# design.net
KiCad netlist of a schematic drawn in Altium Designer
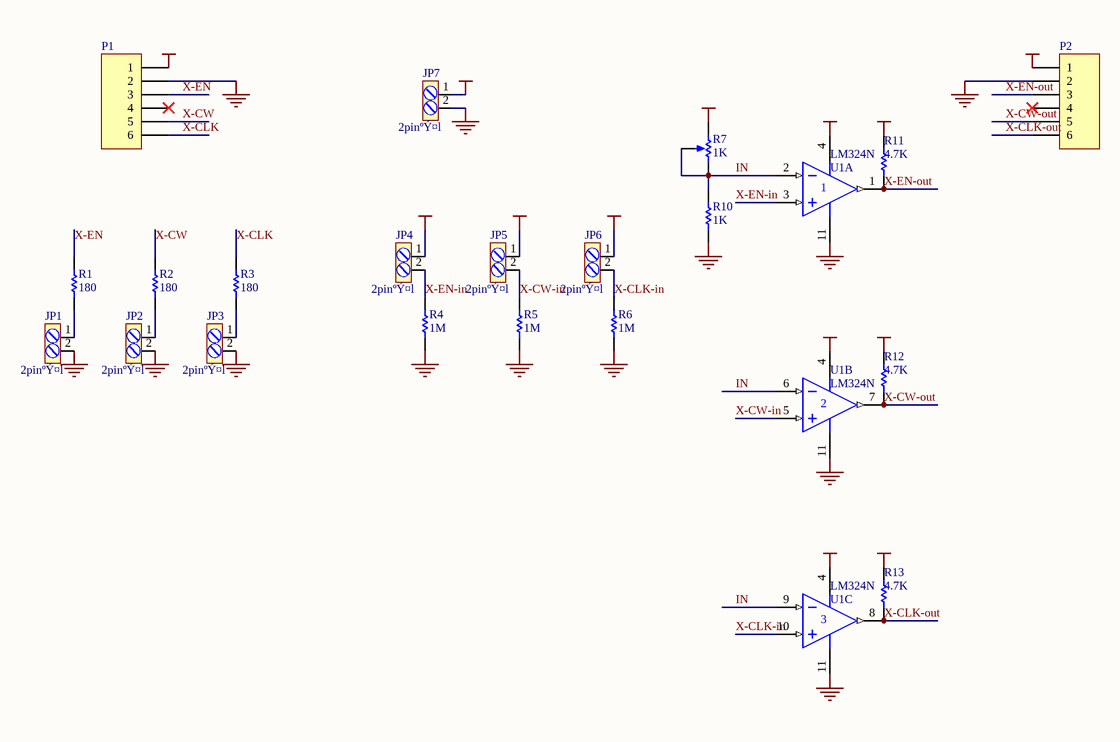
[diagram p0: 光纖發射.SCHDOC]

(export (version "E")
  (design (tool "Eeschema 10.0.6"))
  (components
    (comp (ref "JP1") (value "2pinºÝ¤l") (footprint "2PINºÝ¤l-1") (libsource (lib "") (part "2pinºÝ¤l_1")))
    (comp (ref "JP2")
      (value "2pinºÝ¤l")
      (footprint "2PINºÝ¤l-1")
      (libsource (lib "mydata") (part "2pinºÝ¤l"))
    )
    (comp (ref "JP3")
      (value "2pinºÝ¤l")
      (footprint "2PINºÝ¤l-1")
      (libsource (lib "mydata") (part "2pinºÝ¤l"))
    )
    (comp (ref "JP4")
      (value "2pinºÝ¤l")
      (footprint "2PINºÝ¤l-1")
      (libsource (lib "mydata") (part "2pinºÝ¤l"))
    )
    (comp (ref "JP5")
      (value "2pinºÝ¤l")
      (footprint "2PINºÝ¤l-1")
      (libsource (lib "mydata") (part "2pinºÝ¤l"))
    )
    (comp (ref "JP6")
      (value "2pinºÝ¤l")
      (footprint "2PINºÝ¤l-1")
      (libsource (lib "mydata") (part "2pinºÝ¤l"))
    )
    (comp (ref "JP7")
      (value "2pinºÝ¤l")
      (footprint "2PINºÝ¤l-1")
      (libsource (lib "mydata") (part "2pinºÝ¤l"))
    )
    (comp (ref "P1")
      (value "Header 6")
      (footprint "HDR1X6")
      (description "Header, 6-Pin")
      (fields (field (name "PUBLISHER") "Altium Limited"))
      (libsource (lib "") (part "Header 6_1"))
    )
    (comp (ref "P2")
      (value "Header 6")
      (footprint "HDR1X6")
      (description "Header, 6-Pin")
      (fields (field (name "PUBLISHER") "Altium Limited"))
      (libsource (lib "Miscellaneous Connectors") (part "Header 6"))
    )
    (comp (ref "R1")
      (value "180")
      (footprint "AXIAL-0.3")
      (description "Resistor")
      (fields (field (name "Comment") "Res1") (field (name "PUBLISHER") "Altium Limited"))
      (libsource (lib "Miscellaneous Devices") (part "Res1"))
    )
    (comp (ref "R2")
      (value "180")
      (footprint "AXIAL-0.3")
      (description "Resistor")
      (fields (field (name "Comment") "Res1") (field (name "PUBLISHER") "Altium Limited"))
      (libsource (lib "Miscellaneous Devices") (part "Res1"))
    )
    (comp (ref "R3")
      (value "180")
      (footprint "AXIAL-0.3")
      (description "Resistor")
      (fields (field (name "Comment") "Res1") (field (name "PUBLISHER") "Altium Limited"))
      (libsource (lib "Miscellaneous Devices") (part "Res1"))
    )
    (comp (ref "R4")
      (value "1M")
      (footprint "AXIAL-0.3")
      (description "Resistor")
      (fields (field (name "Comment") "Res1") (field (name "PUBLISHER") "Altium Limited"))
      (libsource (lib "Miscellaneous Devices") (part "Res1"))
    )
    (comp (ref "R5")
      (value "1M")
      (footprint "AXIAL-0.3")
      (description "Resistor")
      (fields (field (name "Comment") "Res1") (field (name "PUBLISHER") "Altium Limited"))
      (libsource (lib "Miscellaneous Devices") (part "Res1"))
    )
    (comp (ref "R6")
      (value "1M")
      (footprint "AXIAL-0.3")
      (description "Resistor")
      (fields (field (name "Comment") "Res1") (field (name "PUBLISHER") "Altium Limited"))
      (libsource (lib "Miscellaneous Devices") (part "Res1"))
    )
    (comp (ref "R7")
      (value "1K")
      (footprint "VR1")
      (description "Potentiometer")
      (fields (field (name "Comment") "RPot") (field (name "PUBLISHER") "Altium Limited"))
      (libsource (lib "Miscellaneous Devices") (part "RPot"))
    )
    (comp (ref "R10")
      (value "1K")
      (footprint "AXIAL-0.3")
      (description "Resistor")
      (fields (field (name "Comment") "Res1") (field (name "PUBLISHER") "Altium Limited"))
      (libsource (lib "Miscellaneous Devices") (part "Res1"))
    )
    (comp (ref "R11")
      (value "4.7K")
      (footprint "AXIAL-0.3")
      (description "Resistor")
      (fields (field (name "Comment") "Res1") (field (name "PUBLISHER") "Altium Limited"))
      (libsource (lib "Miscellaneous Devices") (part "Res1"))
    )
    (comp (ref "R12")
      (value "4.7K")
      (footprint "AXIAL-0.3")
      (description "Resistor")
      (fields (field (name "Comment") "Res1") (field (name "PUBLISHER") "Altium Limited"))
      (libsource (lib "Miscellaneous Devices") (part "Res1"))
    )
    (comp (ref "R13")
      (value "4.7K")
      (footprint "AXIAL-0.3")
      (description "Resistor")
      (fields (field (name "Comment") "Res1") (field (name "PUBLISHER") "Altium Limited"))
      (libsource (lib "Miscellaneous Devices") (part "Res1"))
    )
    (comp (ref "U1")
      (value "LM324N")
      (footprint "646-06")
      (description "Quad Low-Power Operational Amplifier")
      (fields (field (name "PUBLISHER") "Altium Limited"))
      (libsource (lib "Motorola Amplifier Operational Amplifier") (part "LM324N"))
    )
  )
  (nets
    (net (code "1") (name "+5") (class "Default")
      (node (ref "JP4") (pin "1") (pinfunction "1_1") (pintype "passive"))
      (node (ref "JP5") (pin "1") (pinfunction "1_1") (pintype "passive"))
      (node (ref "JP6") (pin "1") (pinfunction "1_1") (pintype "passive"))
      (node (ref "JP7") (pin "1") (pinfunction "1_1") (pintype "passive"))
      (node (ref "P2") (pin "1") (pinfunction "1_1") (pintype "passive"))
      (node (ref "R11") (pin "2") (pinfunction "2_2") (pintype "passive"))
      (node (ref "R12") (pin "2") (pinfunction "2_2") (pintype "passive"))
      (node (ref "R13") (pin "2") (pinfunction "2_2") (pintype "passive"))
      (node (ref "R7") (pin "1") (pinfunction "TOP_1") (pintype "passive"))
      (node (ref "U1") (pin "4") (pinfunction "V+_4") (pintype "power_in"))
    )
    (net (code "2") (name "/IN") (class "Default")
      (node (ref "R10") (pin "2") (pinfunction "2_2") (pintype "passive"))
      (node (ref "R7") (pin "2") (pinfunction "BOT_2") (pintype "passive"))
      (node (ref "R7") (pin "3") (pinfunction "TAP_3") (pintype "passive"))
      (node (ref "U1") (pin "2") (pinfunction "IN-_2") (pintype "input"))
      (node (ref "U1") (pin "6") (pinfunction "IN-_6") (pintype "input"))
      (node (ref "U1") (pin "9") (pinfunction "IN-_9") (pintype "input"))
    )
    (net (code "3") (name "/X-CLK") (class "Default")
      (node (ref "P1") (pin "6") (pinfunction "6_6") (pintype "passive"))
      (node (ref "R3") (pin "1") (pinfunction "1_1") (pintype "passive"))
    )
    (net (code "4") (name "/X-CLK-in") (class "Default")
      (node (ref "JP6") (pin "2") (pinfunction "2_2") (pintype "passive"))
      (node (ref "R6") (pin "1") (pinfunction "1_1") (pintype "passive"))
      (node (ref "U1") (pin "10") (pinfunction "IN+_10") (pintype "input"))
    )
    (net (code "5") (name "/X-CLK-out") (class "Default")
      (node (ref "P2") (pin "6") (pinfunction "6_6") (pintype "passive"))
      (node (ref "R13") (pin "1") (pinfunction "1_1") (pintype "passive"))
      (node (ref "U1") (pin "8") (pinfunction "OUT_8") (pintype "output"))
    )
    (net (code "6") (name "/X-CW") (class "Default")
      (node (ref "P1") (pin "5") (pinfunction "5_5") (pintype "passive"))
      (node (ref "R2") (pin "1") (pinfunction "1_1") (pintype "passive"))
    )
    (net (code "7") (name "/X-CW-in") (class "Default")
      (node (ref "JP5") (pin "2") (pinfunction "2_2") (pintype "passive"))
      (node (ref "R5") (pin "1") (pinfunction "1_1") (pintype "passive"))
      (node (ref "U1") (pin "5") (pinfunction "IN+_5") (pintype "input"))
    )
    (net (code "8") (name "/X-CW-out") (class "Default")
      (node (ref "P2") (pin "5") (pinfunction "5_5") (pintype "passive"))
      (node (ref "R12") (pin "1") (pinfunction "1_1") (pintype "passive"))
      (node (ref "U1") (pin "7") (pinfunction "OUT_7") (pintype "output"))
    )
    (net (code "9") (name "/X-EN") (class "Default")
      (node (ref "P1") (pin "3") (pinfunction "3_3") (pintype "passive"))
      (node (ref "R1") (pin "2") (pinfunction "2_2") (pintype "passive"))
    )
    (net (code "10") (name "/X-EN-in") (class "Default")
      (node (ref "JP4") (pin "2") (pinfunction "2_2") (pintype "passive"))
      (node (ref "R4") (pin "1") (pinfunction "1_1") (pintype "passive"))
      (node (ref "U1") (pin "3") (pinfunction "IN+_3") (pintype "input"))
    )
    (net (code "11") (name "/X-EN-out") (class "Default")
      (node (ref "P2") (pin "3") (pinfunction "3_3") (pintype "passive"))
      (node (ref "R11") (pin "1") (pinfunction "1_1") (pintype "passive"))
      (node (ref "U1") (pin "1") (pinfunction "OUT_1") (pintype "output"))
    )
    (net (code "12") (name "GND") (class "Default")
      (node (ref "JP1") (pin "2") (pinfunction "2_2") (pintype "passive"))
      (node (ref "JP2") (pin "2") (pinfunction "2_2") (pintype "passive"))
      (node (ref "JP3") (pin "2") (pinfunction "2_2") (pintype "passive"))
      (node (ref "P1") (pin "2") (pinfunction "2_2") (pintype "passive"))
    )
    (net (code "13") (name "GND1") (class "Default")
      (node (ref "JP7") (pin "2") (pinfunction "2_2") (pintype "passive"))
      (node (ref "P2") (pin "2") (pinfunction "2_2") (pintype "passive"))
      (node (ref "R10") (pin "1") (pinfunction "1_1") (pintype "passive"))
      (node (ref "R4") (pin "2") (pinfunction "2_2") (pintype "passive"))
      (node (ref "R5") (pin "2") (pinfunction "2_2") (pintype "passive"))
      (node (ref "R6") (pin "2") (pinfunction "2_2") (pintype "passive"))
      (node (ref "U1") (pin "11") (pinfunction "V-_11") (pintype "power_in"))
    )
    (net (code "14") (name "Net-(JP1-Pad1)") (class "Default")
      (node (ref "JP1") (pin "1") (pinfunction "1_1") (pintype "passive"))
      (node (ref "R1") (pin "1") (pinfunction "1_1") (pintype "passive"))
    )
    (net (code "15") (name "Net-(JP2-Pad1)") (class "Default")
      (node (ref "JP2") (pin "1") (pinfunction "1_1") (pintype "passive"))
      (node (ref "R2") (pin "2") (pinfunction "2_2") (pintype "passive"))
    )
    (net (code "16") (name "Net-(JP3-Pad1)") (class "Default")
      (node (ref "JP3") (pin "1") (pinfunction "1_1") (pintype "passive"))
      (node (ref "R3") (pin "2") (pinfunction "2_2") (pintype "passive"))
    )
    (net (code "17") (name "VCC") (class "Default")
      (node (ref "P1") (pin "1") (pinfunction "1_1") (pintype "passive"))
    )
    (net (code "18") (name "unconnected-(P1-Pad4)") (class "Default")
      (node (ref "P1") (pin "4") (pinfunction "4_4") (pintype "passive+no_connect"))
    )
    (net (code "19") (name "unconnected-(P2-Pad4)") (class "Default")
      (node (ref "P2") (pin "4") (pinfunction "4_4") (pintype "passive+no_connect"))
    )
  )
)
